# HardwareSchematicv2.net
KiCad netlist of a schematic drawn in Altium Designer
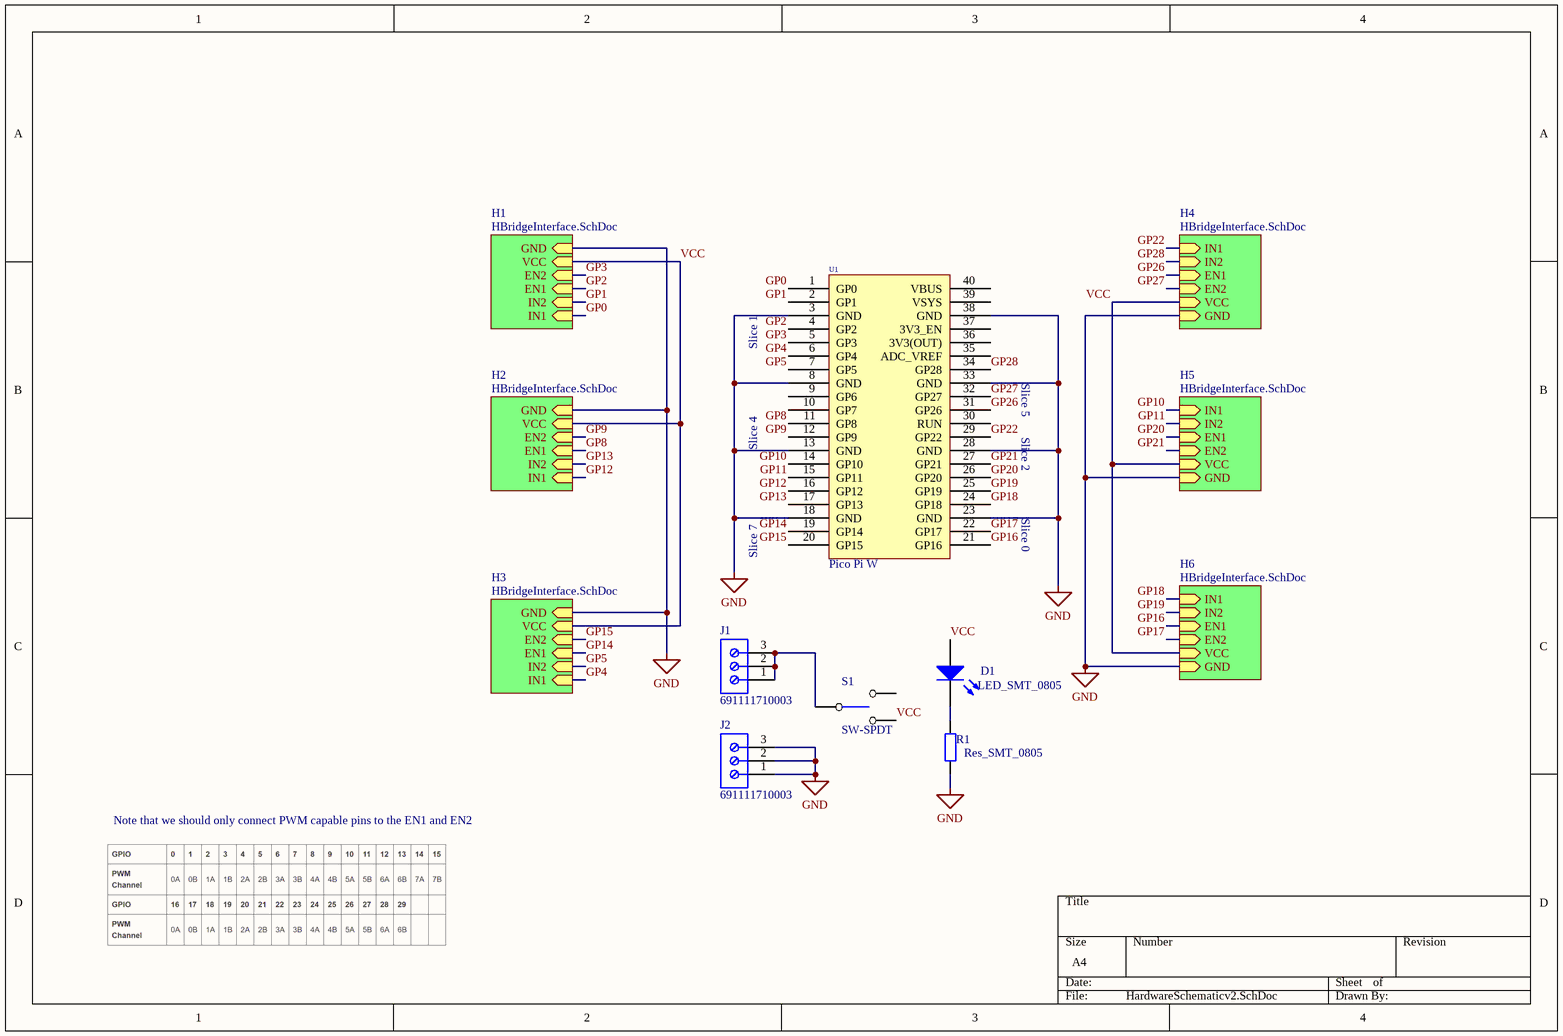
[diagram p0: HardwareSchematicv2.SchDoc]

(export (version "E")
  (design (tool "Eeschema 10.0.6"))
  (components
    (comp (ref "D1")
      (value "LED_SMT_0805")
      (footprint "0805 LED")
      (description "SMT LED 0805 size")
      (fields
        (field (name "MANUFACTURER PART NUMBER") "LTST-C170KGKT")
        (field (name "MANUFACTURER") "Lite-On Inc.")
      )
      (libsource (lib "University of Auckland") (part "LED_SMT_0805"))
    )
    (comp (ref "J1")
      (value "691111710003")
      (footprint "691111710003")
      (fields (field (name "VOLTAGE") "300V"))
      (libsource (lib "Altium Content Vault") (part "TBL - 1R - 03P - Screw"))
    )
    (comp (ref "J2")
      (value "691111710003")
      (footprint "691111710003")
      (fields (field (name "VOLTAGE") "300V"))
      (libsource (lib "Altium Content Vault") (part "TBL - 1R - 03P - Screw"))
    )
    (comp (ref "R1")
      (value "Res_SMT_0805")
      (footprint "0805 RES")
      (description "0805 resistor")
      (fields (field (name "PUBLISHER") "Altium Limited"))
      (libsource (lib "University of Auckland") (part "Res_SMT_0805"))
    )
    (comp (ref "S1")
      (value "SW-SPDT")
      (footprint "SW-SPDT")
      (description "Toggle Switch")
      (libsource (lib "University of Auckland") (part "SW-SPDT"))
    )
    (comp (ref "U1")
      (value "Pico Pi W")
      (footprint "New footprint 1")
      (description "micro")
      (libsource (lib "University of Auckland") (part "Pico Pi W-Symbol-1"))
    )
  )
  (nets
    (net (code "1") (name "/GP0") (class "Default")
      (node (ref "U1") (pin "1") (pinfunction "GP0_1") (pintype "passive"))
    )
    (net (code "2") (name "/GP1") (class "Default")
      (node (ref "U1") (pin "2") (pinfunction "GP1_2") (pintype "passive"))
    )
    (net (code "3") (name "/GP2") (class "Default")
      (node (ref "U1") (pin "4") (pinfunction "GP2_4") (pintype "passive"))
    )
    (net (code "4") (name "/GP3") (class "Default")
      (node (ref "U1") (pin "5") (pinfunction "GP3_5") (pintype "passive"))
    )
    (net (code "5") (name "/GP4") (class "Default")
      (node (ref "U1") (pin "6") (pinfunction "GP4_6") (pintype "passive"))
    )
    (net (code "6") (name "/GP5") (class "Default")
      (node (ref "U1") (pin "7") (pinfunction "GP5_7") (pintype "passive"))
    )
    (net (code "7") (name "/GP8") (class "Default")
      (node (ref "U1") (pin "11") (pinfunction "GP8_11") (pintype "passive"))
    )
    (net (code "8") (name "/GP9") (class "Default")
      (node (ref "U1") (pin "12") (pinfunction "GP9_12") (pintype "passive"))
    )
    (net (code "9") (name "/GP10") (class "Default")
      (node (ref "U1") (pin "14") (pinfunction "GP10_14") (pintype "passive"))
    )
    (net (code "10") (name "/GP11") (class "Default")
      (node (ref "U1") (pin "15") (pinfunction "GP11_15") (pintype "passive"))
    )
    (net (code "11") (name "/GP12") (class "Default")
      (node (ref "U1") (pin "16") (pinfunction "GP12_16") (pintype "passive"))
    )
    (net (code "12") (name "/GP13") (class "Default")
      (node (ref "U1") (pin "17") (pinfunction "GP13_17") (pintype "passive"))
    )
    (net (code "13") (name "/GP14") (class "Default")
      (node (ref "U1") (pin "19") (pinfunction "GP14_19") (pintype "passive"))
    )
    (net (code "14") (name "/GP15") (class "Default")
      (node (ref "U1") (pin "20") (pinfunction "GP15_20") (pintype "passive"))
    )
    (net (code "15") (name "/GP16") (class "Default")
      (node (ref "U1") (pin "21") (pinfunction "GP16_21") (pintype "passive"))
    )
    (net (code "16") (name "/GP17") (class "Default")
      (node (ref "U1") (pin "22") (pinfunction "GP17_22") (pintype "passive"))
    )
    (net (code "17") (name "/GP18") (class "Default")
      (node (ref "U1") (pin "24") (pinfunction "GP18_24") (pintype "passive"))
    )
    (net (code "18") (name "/GP19") (class "Default")
      (node (ref "U1") (pin "25") (pinfunction "GP19_25") (pintype "passive"))
    )
    (net (code "19") (name "/GP20") (class "Default")
      (node (ref "U1") (pin "26") (pinfunction "GP20_26") (pintype "passive"))
    )
    (net (code "20") (name "/GP21") (class "Default")
      (node (ref "U1") (pin "27") (pinfunction "GP21_27") (pintype "passive"))
    )
    (net (code "21") (name "/GP22") (class "Default")
      (node (ref "U1") (pin "29") (pinfunction "GP22_29") (pintype "passive"))
    )
    (net (code "22") (name "/GP26") (class "Default")
      (node (ref "U1") (pin "31") (pinfunction "GP26_31") (pintype "passive"))
    )
    (net (code "23") (name "/GP27") (class "Default")
      (node (ref "U1") (pin "32") (pinfunction "GP27_32") (pintype "passive"))
    )
    (net (code "24") (name "/GP28") (class "Default")
      (node (ref "U1") (pin "34") (pinfunction "GP28_34") (pintype "passive"))
    )
    (net (code "25") (name "/VCC") (class "Default")
      (node (ref "D1") (pin "1") (pinfunction "A_1") (pintype "passive"))
      (node (ref "S1") (pin "3") (pinfunction "3_3") (pintype "passive"))
    )
    (net (code "26") (name "GND") (class "Default")
      (node (ref "J2") (pin "1") (pinfunction "1_1") (pintype "passive"))
      (node (ref "J2") (pin "2") (pinfunction "2_2") (pintype "passive"))
      (node (ref "J2") (pin "3") (pinfunction "3_3") (pintype "passive"))
      (node (ref "R1") (pin "2") (pinfunction "2_2") (pintype "passive"))
      (node (ref "U1") (pin "13") (pinfunction "GND_13") (pintype "passive"))
      (node (ref "U1") (pin "18") (pinfunction "GND_18") (pintype "passive"))
      (node (ref "U1") (pin "23") (pinfunction "GND_23") (pintype "passive"))
      (node (ref "U1") (pin "28") (pinfunction "GND_28") (pintype "passive"))
      (node (ref "U1") (pin "3") (pinfunction "GND_3") (pintype "passive"))
      (node (ref "U1") (pin "33") (pinfunction "GND_33") (pintype "passive"))
      (node (ref "U1") (pin "38") (pinfunction "GND_38") (pintype "passive"))
      (node (ref "U1") (pin "8") (pinfunction "GND_8") (pintype "passive"))
    )
    (net (code "27") (name "Net-(D1-K)") (class "Default")
      (node (ref "D1") (pin "2") (pinfunction "K_2") (pintype "passive"))
      (node (ref "R1") (pin "1") (pinfunction "1_1") (pintype "passive"))
    )
    (net (code "28") (name "Net-(J1-Pad1)") (class "Default")
      (node (ref "J1") (pin "1") (pinfunction "1_1") (pintype "passive"))
      (node (ref "J1") (pin "2") (pinfunction "2_2") (pintype "passive"))
      (node (ref "J1") (pin "3") (pinfunction "3_3") (pintype "passive"))
      (node (ref "S1") (pin "2") (pinfunction "2_2") (pintype "passive"))
    )
    (net (code "29") (name "unconnected-(S1-Pad1)") (class "Default")
      (node (ref "S1") (pin "1") (pinfunction "1_1") (pintype "passive"))
    )
    (net (code "30") (name "unconnected-(U1-3V3(OUT)-Pad36)") (class "Default")
      (node (ref "U1") (pin "36") (pinfunction "3V3(OUT)_36") (pintype "passive"))
    )
    (net (code "31") (name "unconnected-(U1-3V3_EN-Pad37)") (class "Default")
      (node (ref "U1") (pin "37") (pinfunction "3V3_EN_37") (pintype "passive"))
    )
    (net (code "32") (name "unconnected-(U1-ADC_VREF-Pad35)") (class "Default")
      (node (ref "U1") (pin "35") (pinfunction "ADC_VREF_35") (pintype "passive"))
    )
    (net (code "33") (name "unconnected-(U1-GP6-Pad9)") (class "Default")
      (node (ref "U1") (pin "9") (pinfunction "GP6_9") (pintype "passive"))
    )
    (net (code "34") (name "unconnected-(U1-GP7-Pad10)") (class "Default")
      (node (ref "U1") (pin "10") (pinfunction "GP7_10") (pintype "passive"))
    )
    (net (code "35") (name "unconnected-(U1-RUN-Pad30)") (class "Default")
      (node (ref "U1") (pin "30") (pinfunction "RUN_30") (pintype "passive"))
    )
    (net (code "36") (name "unconnected-(U1-VBUS-Pad40)") (class "Default")
      (node (ref "U1") (pin "40") (pinfunction "VBUS_40") (pintype "passive"))
    )
    (net (code "37") (name "unconnected-(U1-VSYS-Pad39)") (class "Default")
      (node (ref "U1") (pin "39") (pinfunction "VSYS_39") (pintype "passive"))
    )
  )
)
